# DOWNSTREAM.net
KiCad netlist of a schematic drawn in Altium Designer
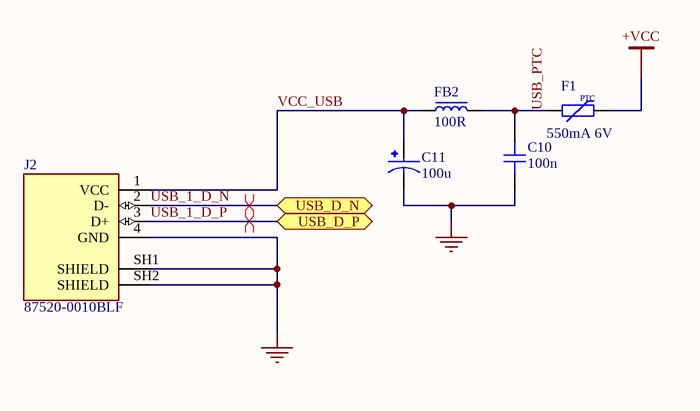
[diagram p0: DOWNSTREAM.SchDoc]

(export (version "E")
  (design (tool "Eeschema 10.0.6"))
  (components
    (comp (ref "C10")
      (value "100n")
      (footprint "CAP_0805")
      (description "Capacitor SMD 0805")
      (libsource (lib "Schematic-Lib-PhilsLab") (part "CAP_0805"))
    )
    (comp (ref "C11")
      (value "100u")
      (footprint "CAP_EEEHA0J101WR")
      (fields (field (name "MF") "Panasonic Electronic") (field (name "MP") "EEE-HA0J101WR"))
      (libsource (lib "Schematic-Lib-PhilsLab") (part "EEEHA0J101WR"))
    )
    (comp (ref "F1")
      (value "550mA 6V")
      (footprint "FUSE_1206")
      (description "Fuse PPTC SMD 1206")
      (libsource (lib "Schematic-Lib-PhilsLab") (part "FUSE_PPTC_1206"))
    )
    (comp (ref "FB2")
      (value "100R")
      (footprint "FB_0603")
      (description "Ferrite Bead SMD 0603")
      (libsource (lib "Schematic-Lib-PhilsLab") (part "FB_0603"))
    )
    (comp (ref "J2")
      (value "87520-0010BLF")
      (footprint "AMPHENOL_87520-0010BLF")
      (fields (field (name "MF") "AMPHENOL ICC / FCI"))
      (libsource (lib "Schematic-Lib-PhilsLab") (part "87520-0010BLF"))
    )
  )
  (nets
    (net (code "1") (name "+VCC") (class "Default")
      (node (ref "F1") (pin "2") (pinfunction "2_2") (pintype "passive"))
    )
    (net (code "2") (name "/USB_1_D_N") (class "Default")
      (node (ref "J2") (pin "2") (pinfunction "D-_2") (pintype "bidirectional"))
    )
    (net (code "3") (name "/USB_1_D_P") (class "Default")
      (node (ref "J2") (pin "3") (pinfunction "D+_3") (pintype "bidirectional"))
    )
    (net (code "4") (name "/USB_PTC") (class "Default")
      (node (ref "C10") (pin "2") (pinfunction "2_2") (pintype "passive"))
      (node (ref "F1") (pin "1") (pinfunction "1_1") (pintype "passive"))
      (node (ref "FB2") (pin "2") (pinfunction "2_2") (pintype "passive"))
    )
    (net (code "5") (name "/VCC_USB") (class "Default")
      (node (ref "C11") (pin "1") (pinfunction "1_1") (pintype "passive"))
      (node (ref "FB2") (pin "1") (pinfunction "1_1") (pintype "passive"))
      (node (ref "J2") (pin "1") (pinfunction "VCC_1") (pintype "power_in"))
    )
    (net (code "6") (name "GND") (class "Default")
      (node (ref "C10") (pin "1") (pinfunction "1_1") (pintype "passive"))
      (node (ref "C11") (pin "2") (pinfunction "2_2") (pintype "passive"))
      (node (ref "J2") (pin "4") (pinfunction "GND_4") (pintype "power_in"))
      (node (ref "J2") (pin "SH1") (pinfunction "SHIELD_SH1") (pintype "passive"))
      (node (ref "J2") (pin "SH2") (pinfunction "SHIELD_SH2") (pintype "passive"))
    )
  )
)
